# SCH_Schema_Line_Follower_2_2023-12-11.net
KiCad netlist of a schematic drawn in EasyEDA
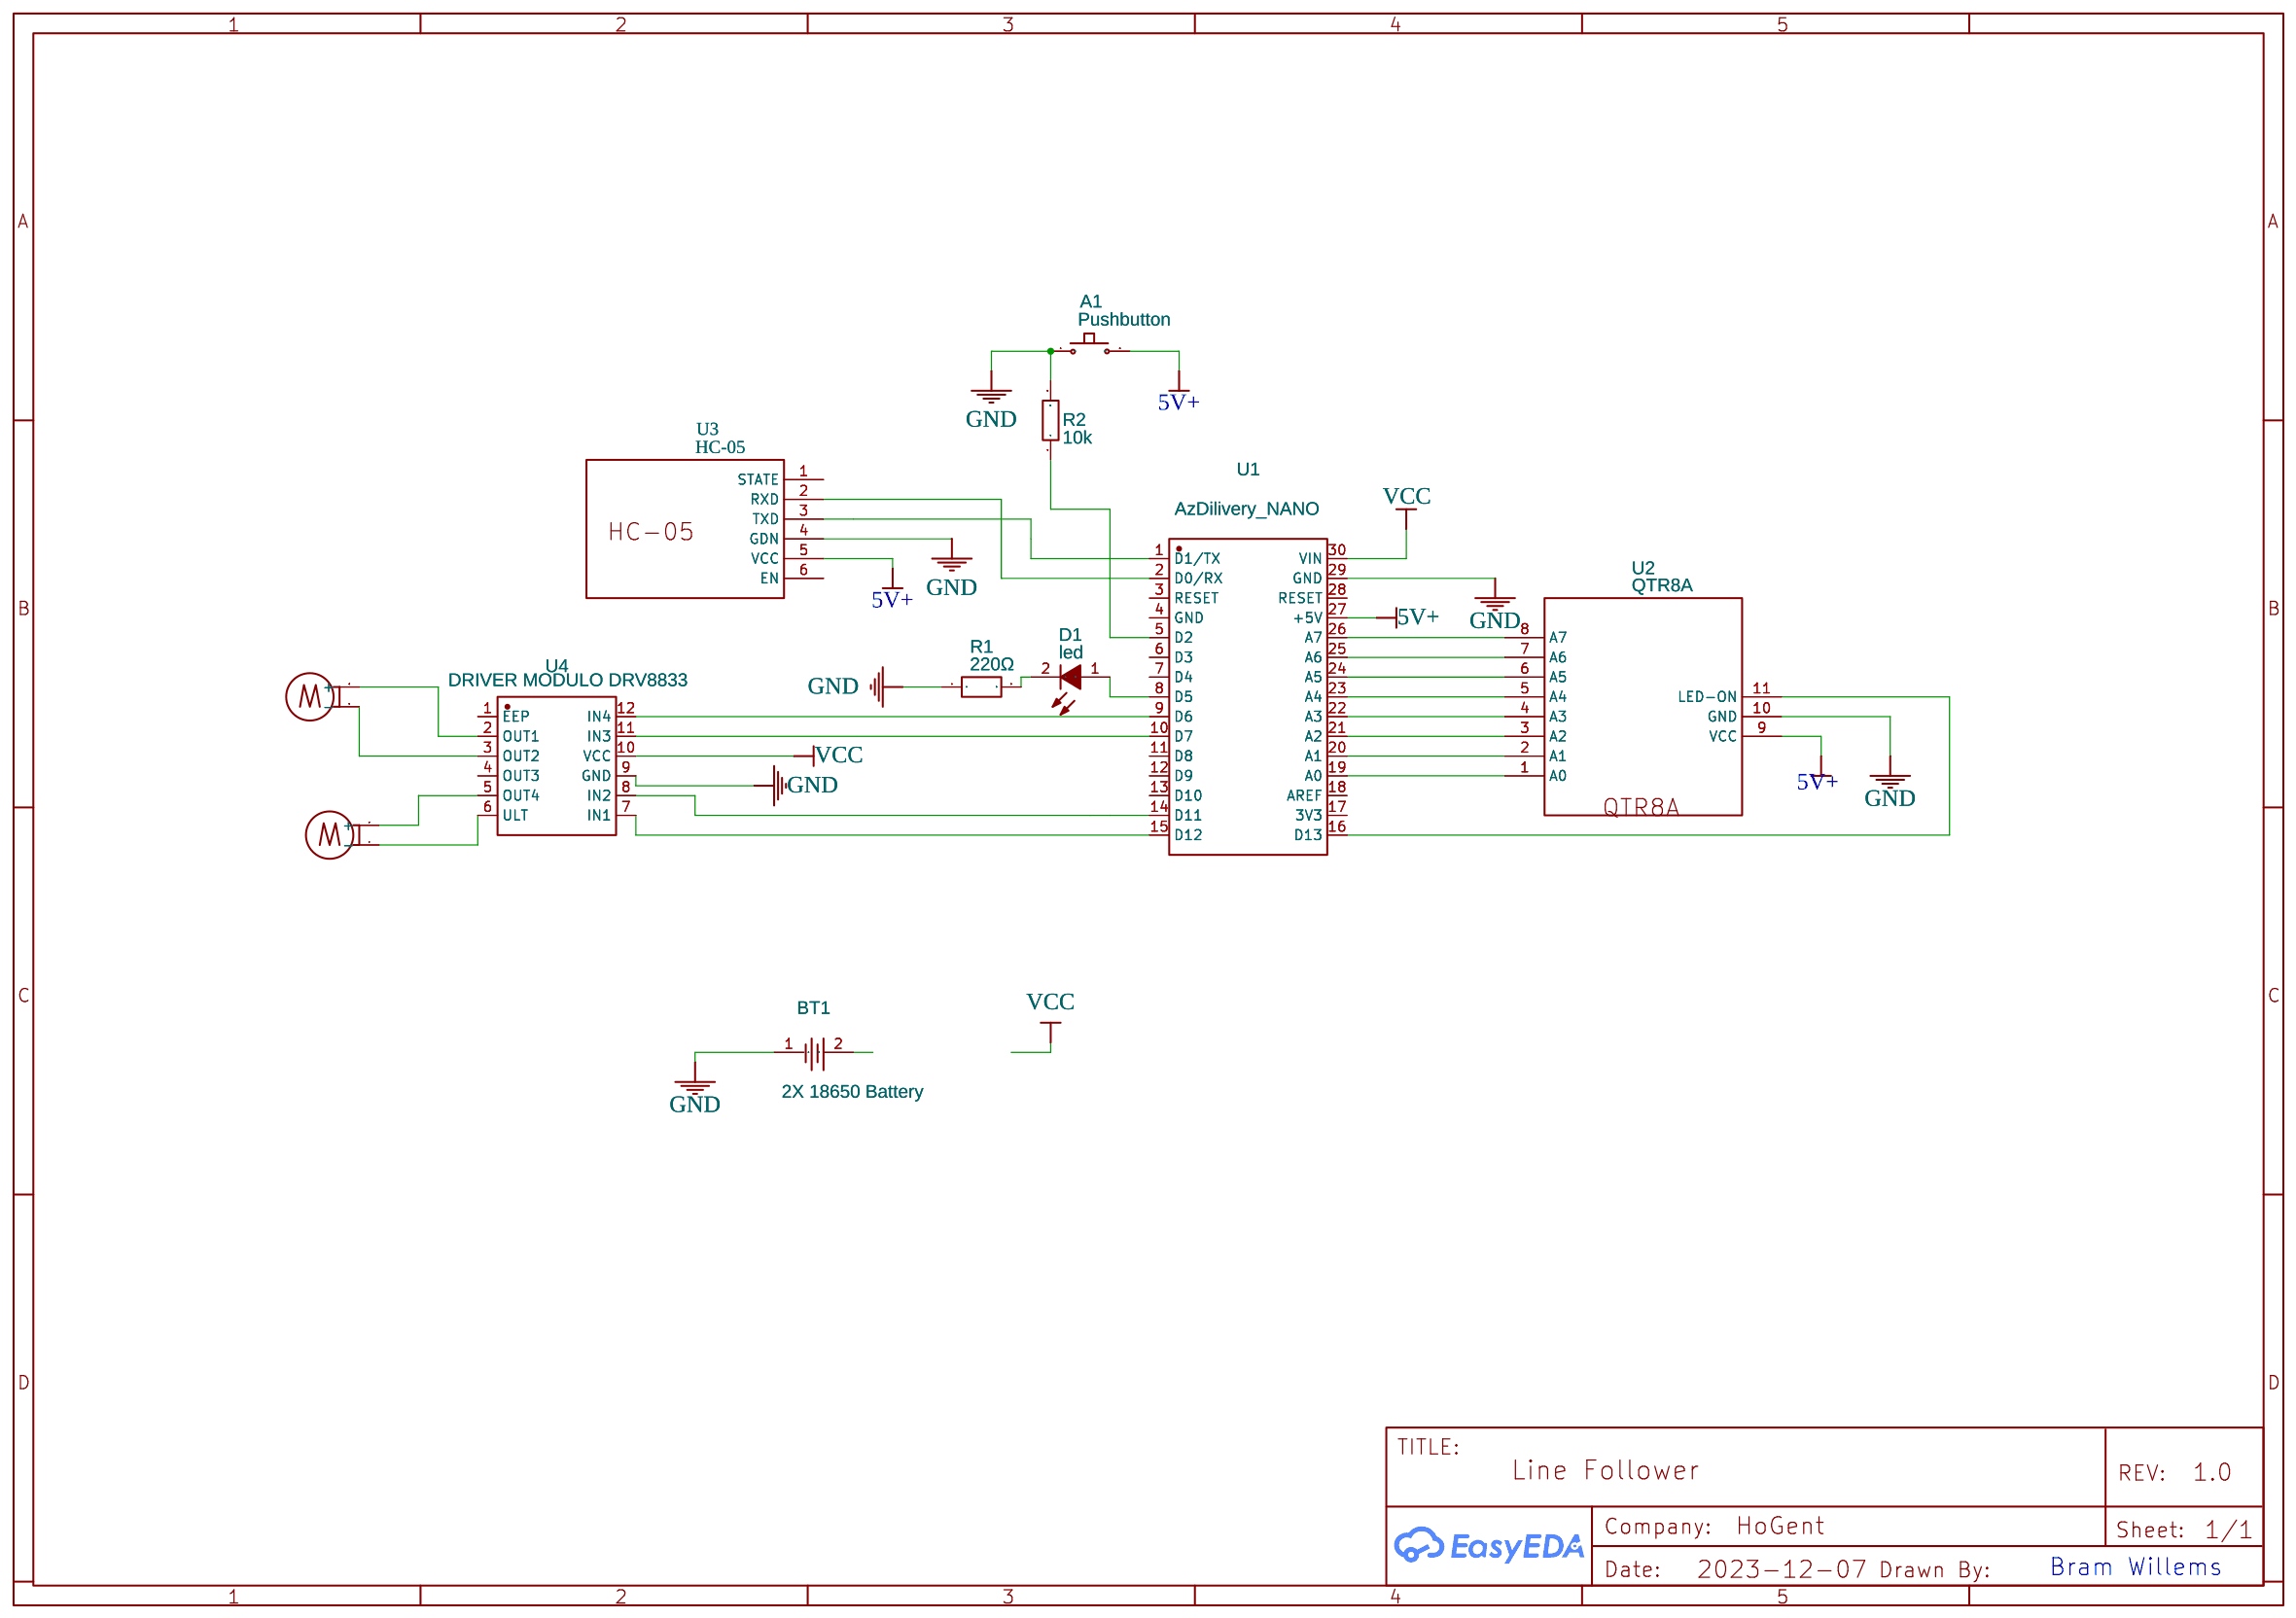
[diagram p0: schematic sheet]

(export (version "E")
  (design (tool "Eeschema 10.0.6"))
  (components
    (comp (ref "A1") (value "Pushbutton") (libsource (lib "") (part "Ammeter")))
    (comp (ref "BT1")
      (value "2X 18650 Battery")
      (fields
        (field (name "Manufacturer Part") "BH-18650-A1AJ006")
        (field (name "Manufacturer") "MYOUNG(美阳)")
      )
      (libsource (lib "") (part "BH-18650-A1AJ006"))
    )
    (comp (ref "D1")
      (value "led")
      (fields (field (name "Manufacturer Part") "5600") (field (name "Manufacturer") "VccLite"))
      (libsource (lib "") (part "3MM GREEN TH LED 5600 COPY"))
    )
    (comp (ref "MQT1")
      (value "LCM1234A3523F")
      (fields (field (name "Manufacturer") "LEADER(立得)"))
      (libsource (lib "") (part "LCM1234A3523F"))
    )
    (comp (ref "MQT2")
      (value "LCM1234A3523F")
      (fields (field (name "Manufacturer") "LEADER(立得)"))
      (libsource (lib "") (part "LCM1234A3523F"))
    )
    (comp (ref "R1")
      (value "220Ω")
      (libsource (lib "") (part "AXIAL RESISTOR 220 OHM - TH_BD2.3-L6.0-P10.00-D0.4"))
    )
    (comp (ref "R2")
      (value "10k")
      (fields (field (name "Manufacturer Part") "RNCP1206FTD10K0"))
      (libsource (lib "") (part "RNCP1206FTD10K0"))
    )
    (comp (ref "U1")
      (value "AzDilivery_NANO")
      (fields (field (name "Manufacturer Part") "ARDUINO_NANO"))
      (libsource (lib "") (part "ARDUINO_NANO"))
    )
    (comp (ref "U2")
      (value "QTR8A")
      (fields (field (name "Manufacturer") "POLOLU"))
      (libsource (lib "") (part "QTR8A"))
    )
    (comp (ref "U3") (value "HC-05") (libsource (lib "") (part "Unknown_350_-550")))
    (comp (ref "U4") (value "DRIVER MODULO DRV8833") (libsource (lib "") (part "DRIVER MODULO DRV8833")))
  )
  (nets
    (net (code "1") (name "5V+") (class "Default")
      (node (ref "A1") (pin "2") (pinfunction "2_2") (pintype "unspecified"))
      (node (ref "U1") (pin "27") (pinfunction "+5V_27") (pintype "unspecified"))
      (node (ref "U2") (pin "9") (pinfunction "VCC_9") (pintype "unspecified"))
      (node (ref "U3") (pin "5") (pinfunction "VCC_5") (pintype "unspecified"))
    )
    (net (code "2") (name "GND") (class "Default")
      (node (ref "A1") (pin "1") (pinfunction "+_1") (pintype "unspecified"))
      (node (ref "BT1") (pin "1") (pinfunction "1_1") (pintype "input"))
      (node (ref "R1") (pin "1") (pinfunction "1_1") (pintype "unspecified"))
      (node (ref "R2") (pin "2") (pinfunction "2_2") (pintype "unspecified"))
      (node (ref "U1") (pin "29") (pinfunction "GND_29") (pintype "unspecified"))
      (node (ref "U2") (pin "10") (pinfunction "GND_10") (pintype "unspecified"))
      (node (ref "U3") (pin "4") (pinfunction "GDN_4") (pintype "unspecified"))
      (node (ref "U4") (pin "9") (pinfunction "GND_9") (pintype "unspecified"))
    )
    (net (code "3") (name "Net-(D1-A)") (class "Default")
      (node (ref "D1") (pin "1") (pinfunction "A_1") (pintype "unspecified"))
      (node (ref "U1") (pin "8") (pinfunction "D5_8") (pintype "unspecified"))
    )
    (net (code "4") (name "Net-(D1-K)") (class "Default")
      (node (ref "D1") (pin "2") (pinfunction "K_2") (pintype "unspecified"))
      (node (ref "R1") (pin "2") (pinfunction "2_2") (pintype "unspecified"))
    )
    (net (code "5") (name "Net-(MQT1-+)") (class "Default")
      (node (ref "MQT1") (pin "2") (pinfunction "+_2") (pintype "unspecified"))
      (node (ref "U4") (pin "2") (pinfunction "OUT1_2") (pintype "unspecified"))
    )
    (net (code "6") (name "Net-(MQT1--)") (class "Default")
      (node (ref "MQT1") (pin "1") (pinfunction "-_1") (pintype "unspecified"))
      (node (ref "U4") (pin "3") (pinfunction "OUT2_3") (pintype "unspecified"))
    )
    (net (code "7") (name "Net-(MQT2-+)") (class "Default")
      (node (ref "MQT2") (pin "2") (pinfunction "+_2") (pintype "unspecified"))
      (node (ref "U4") (pin "5") (pinfunction "OUT4_5") (pintype "unspecified"))
    )
    (net (code "8") (name "Net-(MQT2--)") (class "Default")
      (node (ref "MQT2") (pin "1") (pinfunction "-_1") (pintype "unspecified"))
      (node (ref "U4") (pin "6") (pinfunction "ULT_6") (pintype "unspecified"))
    )
    (net (code "9") (name "Net-(U1-A0)") (class "Default")
      (node (ref "U1") (pin "19") (pinfunction "A0_19") (pintype "unspecified"))
      (node (ref "U2") (pin "1") (pinfunction "A0_1") (pintype "unspecified"))
    )
    (net (code "10") (name "Net-(U1-A1)") (class "Default")
      (node (ref "U1") (pin "20") (pinfunction "A1_20") (pintype "unspecified"))
      (node (ref "U2") (pin "2") (pinfunction "A1_2") (pintype "unspecified"))
    )
    (net (code "11") (name "Net-(U1-A2)") (class "Default")
      (node (ref "U1") (pin "21") (pinfunction "A2_21") (pintype "unspecified"))
      (node (ref "U2") (pin "3") (pinfunction "A2_3") (pintype "unspecified"))
    )
    (net (code "12") (name "Net-(U1-A3)") (class "Default")
      (node (ref "U1") (pin "22") (pinfunction "A3_22") (pintype "unspecified"))
      (node (ref "U2") (pin "4") (pinfunction "A3_4") (pintype "unspecified"))
    )
    (net (code "13") (name "Net-(U1-A4)") (class "Default")
      (node (ref "U1") (pin "23") (pinfunction "A4_23") (pintype "unspecified"))
      (node (ref "U2") (pin "5") (pinfunction "A4_5") (pintype "unspecified"))
    )
    (net (code "14") (name "Net-(U1-A5)") (class "Default")
      (node (ref "U1") (pin "24") (pinfunction "A5_24") (pintype "unspecified"))
      (node (ref "U2") (pin "6") (pinfunction "A5_6") (pintype "unspecified"))
    )
    (net (code "15") (name "Net-(U1-A6)") (class "Default")
      (node (ref "U1") (pin "25") (pinfunction "A6_25") (pintype "unspecified"))
      (node (ref "U2") (pin "7") (pinfunction "A6_7") (pintype "unspecified"))
    )
    (net (code "16") (name "Net-(U1-A7)") (class "Default")
      (node (ref "U1") (pin "26") (pinfunction "A7_26") (pintype "unspecified"))
      (node (ref "U2") (pin "8") (pinfunction "A7_8") (pintype "unspecified"))
    )
    (net (code "17") (name "Net-(U1-D0{slash}RX)") (class "Default")
      (node (ref "U1") (pin "2") (pinfunction "D0/RX_2") (pintype "unspecified"))
      (node (ref "U3") (pin "2") (pinfunction "RXD_2") (pintype "unspecified"))
    )
    (net (code "18") (name "Net-(U1-D1{slash}TX)") (class "Default")
      (node (ref "U1") (pin "1") (pinfunction "D1/TX_1") (pintype "unspecified"))
      (node (ref "U3") (pin "3") (pinfunction "TXD_3") (pintype "unspecified"))
    )
    (net (code "19") (name "Net-(U1-D2)") (class "Default")
      (node (ref "R2") (pin "1") (pinfunction "1_1") (pintype "unspecified"))
      (node (ref "U1") (pin "5") (pinfunction "D2_5") (pintype "unspecified"))
    )
    (net (code "20") (name "Net-(U1-D6)") (class "Default")
      (node (ref "U1") (pin "9") (pinfunction "D6_9") (pintype "unspecified"))
      (node (ref "U4") (pin "12") (pinfunction "IN4_12") (pintype "unspecified"))
    )
    (net (code "21") (name "Net-(U1-D7)") (class "Default")
      (node (ref "U1") (pin "10") (pinfunction "D7_10") (pintype "unspecified"))
      (node (ref "U4") (pin "11") (pinfunction "IN3_11") (pintype "unspecified"))
    )
    (net (code "22") (name "Net-(U1-D11)") (class "Default")
      (node (ref "U1") (pin "14") (pinfunction "D11_14") (pintype "unspecified"))
      (node (ref "U4") (pin "8") (pinfunction "IN2_8") (pintype "unspecified"))
    )
    (net (code "23") (name "Net-(U1-D12)") (class "Default")
      (node (ref "U1") (pin "15") (pinfunction "D12_15") (pintype "unspecified"))
      (node (ref "U4") (pin "7") (pinfunction "IN1_7") (pintype "unspecified"))
    )
    (net (code "24") (name "Net-(U1-D13)") (class "Default")
      (node (ref "U1") (pin "16") (pinfunction "D13_16") (pintype "unspecified"))
      (node (ref "U2") (pin "11") (pinfunction "LED-ON_11") (pintype "unspecified"))
    )
    (net (code "25") (name "VCC") (class "Default")
      (node (ref "U1") (pin "30") (pinfunction "VIN_30") (pintype "unspecified"))
      (node (ref "U4") (pin "10") (pinfunction "VCC_10") (pintype "unspecified"))
    )
    (net (code "26") (name "unconnected-(BT1-Pad2)") (class "Default")
      (node (ref "BT1") (pin "2") (pinfunction "2_2") (pintype "input"))
    )
    (net (code "27") (name "unconnected-(U1-3V3-Pad17)") (class "Default")
      (node (ref "U1") (pin "17") (pinfunction "3V3_17") (pintype "unspecified"))
    )
    (net (code "28") (name "unconnected-(U1-AREF-Pad18)") (class "Default")
      (node (ref "U1") (pin "18") (pinfunction "AREF_18") (pintype "unspecified"))
    )
    (net (code "29") (name "unconnected-(U1-D3-Pad6)") (class "Default")
      (node (ref "U1") (pin "6") (pinfunction "D3_6") (pintype "unspecified"))
    )
    (net (code "30") (name "unconnected-(U1-D4-Pad7)") (class "Default")
      (node (ref "U1") (pin "7") (pinfunction "D4_7") (pintype "unspecified"))
    )
    (net (code "31") (name "unconnected-(U1-D8-Pad11)") (class "Default")
      (node (ref "U1") (pin "11") (pinfunction "D8_11") (pintype "unspecified"))
    )
    (net (code "32") (name "unconnected-(U1-D9-Pad12)") (class "Default")
      (node (ref "U1") (pin "12") (pinfunction "D9_12") (pintype "unspecified"))
    )
    (net (code "33") (name "unconnected-(U1-D10-Pad13)") (class "Default")
      (node (ref "U1") (pin "13") (pinfunction "D10_13") (pintype "unspecified"))
    )
    (net (code "34") (name "unconnected-(U1-GND-Pad4)") (class "Default")
      (node (ref "U1") (pin "4") (pinfunction "GND_4") (pintype "unspecified"))
    )
    (net (code "35") (name "unconnected-(U1-RESET-Pad3)") (class "Default")
      (node (ref "U1") (pin "3") (pinfunction "RESET_3") (pintype "unspecified"))
    )
    (net (code "36") (name "unconnected-(U1-RESET-Pad28)") (class "Default")
      (node (ref "U1") (pin "28") (pinfunction "RESET_28") (pintype "unspecified"))
    )
    (net (code "37") (name "unconnected-(U3-EN-Pad6)") (class "Default")
      (node (ref "U3") (pin "6") (pinfunction "EN_6") (pintype "unspecified"))
    )
    (net (code "38") (name "unconnected-(U3-STATE-Pad1)") (class "Default")
      (node (ref "U3") (pin "1") (pinfunction "STATE_1") (pintype "unspecified"))
    )
    (net (code "39") (name "unconnected-(U4-EEP-Pad1)") (class "Default")
      (node (ref "U4") (pin "1") (pinfunction "EEP_1") (pintype "unspecified"))
    )
    (net (code "40") (name "unconnected-(U4-OUT3-Pad4)") (class "Default")
      (node (ref "U4") (pin "4") (pinfunction "OUT3_4") (pintype "unspecified"))
    )
  )
)
